# alfred_pulse.net
KiCad netlist of a schematic drawn in EAGLE
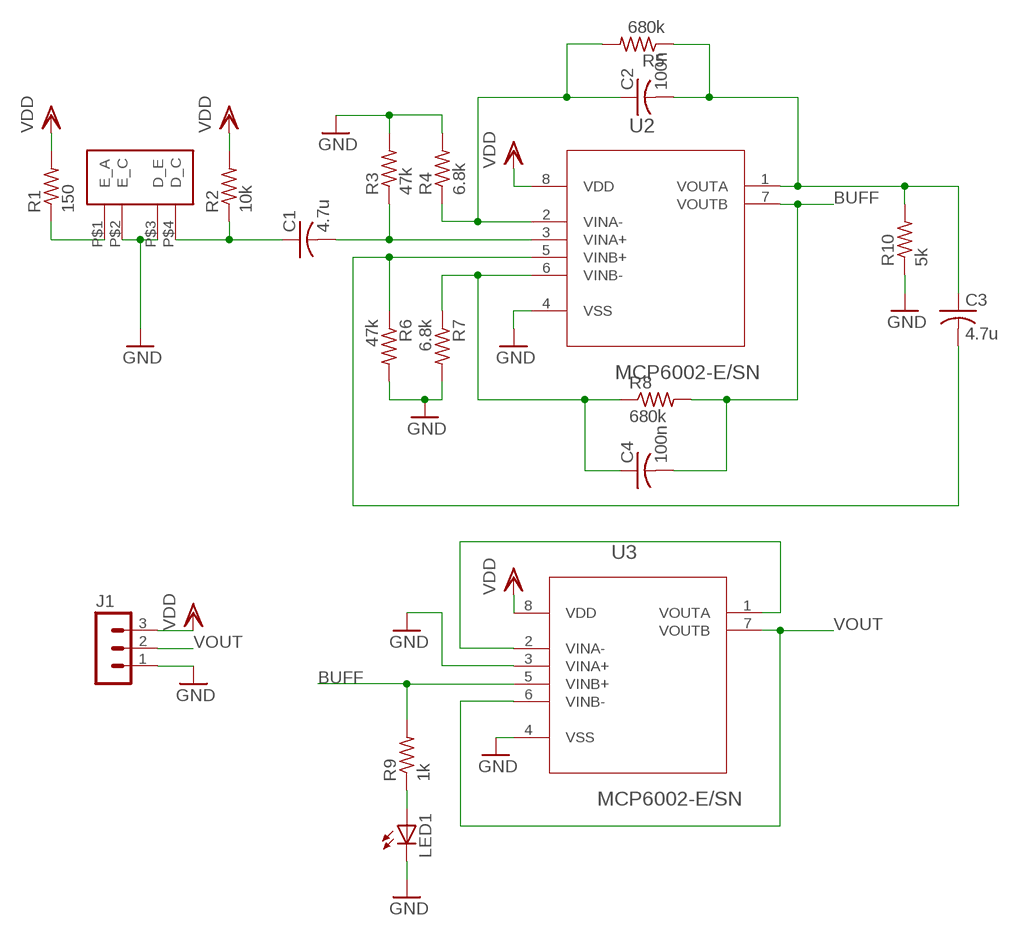
[diagram p0: schematic, sheet 1]

(export (version "E")
  (design (tool "Eeschema 10.0.6"))
  (components
    (comp (ref "C1")
      (value "4.7u")
      (footprint "eagle-import:C0603")
      (libsource (lib "eagle-import") (part "C-USC0603"))
    )
    (comp (ref "C2")
      (value "100n")
      (footprint "eagle-import:C0603")
      (libsource (lib "eagle-import") (part "C-USC0603"))
    )
    (comp (ref "C3")
      (value "4.7u")
      (footprint "eagle-import:C0603")
      (libsource (lib "eagle-import") (part "C-USC0603"))
    )
    (comp (ref "C4")
      (value "100n")
      (footprint "eagle-import:C0603")
      (libsource (lib "eagle-import") (part "C-USC0603"))
    )
    (comp (ref "J1")
      (value "MA03-1")
      (footprint "eagle-import:MA03-1")
      (libsource (lib "eagle-import") (part "MA03-1"))
    )
    (comp (ref "LED1")
      (value "LEDCHIPLED_1206")
      (footprint "eagle-import:CHIPLED_1206")
      (libsource (lib "eagle-import") (part "LEDCHIPLED_1206"))
    )
    (comp (ref "R1")
      (value "150")
      (footprint "eagle-import:R0603")
      (libsource (lib "eagle-import") (part "R-US_R0603"))
    )
    (comp (ref "R2")
      (value "10k")
      (footprint "eagle-import:R0603")
      (libsource (lib "eagle-import") (part "R-US_R0603"))
    )
    (comp (ref "R3")
      (value "47k")
      (footprint "eagle-import:R0603")
      (libsource (lib "eagle-import") (part "R-US_R0603"))
    )
    (comp (ref "R4")
      (value "6.8k")
      (footprint "eagle-import:R0603")
      (libsource (lib "eagle-import") (part "R-US_R0603"))
    )
    (comp (ref "R5")
      (value "680k")
      (footprint "eagle-import:R0603")
      (libsource (lib "eagle-import") (part "R-US_R0603"))
    )
    (comp (ref "R6")
      (value "47k")
      (footprint "eagle-import:R0603")
      (libsource (lib "eagle-import") (part "R-US_R0603"))
    )
    (comp (ref "R7")
      (value "6.8k")
      (footprint "eagle-import:R0603")
      (libsource (lib "eagle-import") (part "R-US_R0603"))
    )
    (comp (ref "R8")
      (value "680k")
      (footprint "eagle-import:R0603")
      (libsource (lib "eagle-import") (part "R-US_R0603"))
    )
    (comp (ref "R9")
      (value "1k")
      (footprint "eagle-import:R0603")
      (libsource (lib "eagle-import") (part "R-US_R0603"))
    )
    (comp (ref "R10")
      (value "5k")
      (footprint "eagle-import:R0603")
      (libsource (lib "eagle-import") (part "R-US_R0603"))
    )
    (comp (ref "U$1")
      (value "TCRT1001")
      (footprint "eagle-import:TCRT1001")
      (libsource (lib "eagle-import") (part "TCRT1001"))
    )
    (comp (ref "U2")
      (value "MCP6002-E/SN")
      (footprint "eagle-import:SOIC127P600X175-8N")
      (libsource (lib "eagle-import") (part "MCP6002-E/SN"))
    )
    (comp (ref "U3")
      (value "MCP6002-E/SN")
      (footprint "eagle-import:SOIC127P600X175-8N")
      (libsource (lib "eagle-import") (part "MCP6002-E/SN"))
    )
  )
  (nets
    (net (code "1") (name "/BUFF") (class "Default")
      (node (ref "C4") (pin "2") (pinfunction "2_2") (pintype "passive"))
      (node (ref "R8") (pin "2") (pinfunction "2_2") (pintype "passive"))
      (node (ref "R9") (pin "2") (pinfunction "2_2") (pintype "passive"))
      (node (ref "U2") (pin "7") (pinfunction "VOUTB_7") (pintype "output"))
      (node (ref "U3") (pin "5") (pinfunction "VINB+_5") (pintype "input"))
    )
    (net (code "2") (name "/VOUT") (class "Default")
      (node (ref "J1") (pin "2") (pinfunction "2_2") (pintype "passive"))
      (node (ref "U3") (pin "6") (pinfunction "VINB-_6") (pintype "input"))
      (node (ref "U3") (pin "7") (pinfunction "VOUTB_7") (pintype "output"))
    )
    (net (code "3") (name "GND") (class "Default")
      (node (ref "J1") (pin "1") (pinfunction "1_1") (pintype "passive"))
      (node (ref "LED1") (pin "C") (pinfunction "C_C") (pintype "passive"))
      (node (ref "R10") (pin "1") (pinfunction "1_1") (pintype "passive"))
      (node (ref "R3") (pin "2") (pinfunction "2_2") (pintype "passive"))
      (node (ref "R4") (pin "2") (pinfunction "2_2") (pintype "passive"))
      (node (ref "R6") (pin "2") (pinfunction "2_2") (pintype "passive"))
      (node (ref "R7") (pin "2") (pinfunction "2_2") (pintype "passive"))
      (node (ref "U$1") (pin "P$2") (pinfunction "E_C_P$2") (pintype "bidirectional"))
      (node (ref "U$1") (pin "P$3") (pinfunction "D_E_P$3") (pintype "bidirectional"))
      (node (ref "U2") (pin "4") (pinfunction "VSS_4") (pintype "power_in"))
      (node (ref "U3") (pin "3") (pinfunction "VINA+_3") (pintype "input"))
      (node (ref "U3") (pin "4") (pinfunction "VSS_4") (pintype "power_in"))
    )
    (net (code "4") (name "Net-(LED1-PadA)") (class "Default")
      (node (ref "LED1") (pin "A") (pinfunction "A_A") (pintype "passive"))
      (node (ref "R9") (pin "1") (pinfunction "1_1") (pintype "passive"))
    )
    (net (code "5") (name "Net-(U$1-D_C)") (class "Default")
      (node (ref "C1") (pin "1") (pinfunction "1_1") (pintype "passive"))
      (node (ref "R2") (pin "1") (pinfunction "1_1") (pintype "passive"))
      (node (ref "U$1") (pin "P$4") (pinfunction "D_C_P$4") (pintype "bidirectional"))
    )
    (net (code "6") (name "Net-(U$1-E_A)") (class "Default")
      (node (ref "R1") (pin "1") (pinfunction "1_1") (pintype "passive"))
      (node (ref "U$1") (pin "P$1") (pinfunction "E_A_P$1") (pintype "bidirectional"))
    )
    (net (code "7") (name "Net-(U2-VINA+)") (class "Default")
      (node (ref "C1") (pin "2") (pinfunction "2_2") (pintype "passive"))
      (node (ref "R3") (pin "1") (pinfunction "1_1") (pintype "passive"))
      (node (ref "U2") (pin "3") (pinfunction "VINA+_3") (pintype "input"))
    )
    (net (code "8") (name "Net-(U2-VINA-)") (class "Default")
      (node (ref "C2") (pin "1") (pinfunction "1_1") (pintype "passive"))
      (node (ref "R4") (pin "1") (pinfunction "1_1") (pintype "passive"))
      (node (ref "R5") (pin "2") (pinfunction "2_2") (pintype "passive"))
      (node (ref "U2") (pin "2") (pinfunction "VINA-_2") (pintype "input"))
    )
    (net (code "9") (name "Net-(U2-VINB+)") (class "Default")
      (node (ref "C3") (pin "2") (pinfunction "2_2") (pintype "passive"))
      (node (ref "R6") (pin "1") (pinfunction "1_1") (pintype "passive"))
      (node (ref "U2") (pin "5") (pinfunction "VINB+_5") (pintype "input"))
    )
    (net (code "10") (name "Net-(U2-VINB-)") (class "Default")
      (node (ref "C4") (pin "1") (pinfunction "1_1") (pintype "passive"))
      (node (ref "R7") (pin "1") (pinfunction "1_1") (pintype "passive"))
      (node (ref "R8") (pin "1") (pinfunction "1_1") (pintype "passive"))
      (node (ref "U2") (pin "6") (pinfunction "VINB-_6") (pintype "input"))
    )
    (net (code "11") (name "Net-(U2-VOUTA)") (class "Default")
      (node (ref "C2") (pin "2") (pinfunction "2_2") (pintype "passive"))
      (node (ref "C3") (pin "1") (pinfunction "1_1") (pintype "passive"))
      (node (ref "R10") (pin "2") (pinfunction "2_2") (pintype "passive"))
      (node (ref "R5") (pin "1") (pinfunction "1_1") (pintype "passive"))
      (node (ref "U2") (pin "1") (pinfunction "VOUTA_1") (pintype "output"))
    )
    (net (code "12") (name "Net-(U3-VINA-)") (class "Default")
      (node (ref "U3") (pin "1") (pinfunction "VOUTA_1") (pintype "output"))
      (node (ref "U3") (pin "2") (pinfunction "VINA-_2") (pintype "input"))
    )
    (net (code "13") (name "VDD") (class "Default")
      (node (ref "J1") (pin "3") (pinfunction "3_3") (pintype "passive"))
      (node (ref "R1") (pin "2") (pinfunction "2_2") (pintype "passive"))
      (node (ref "R2") (pin "2") (pinfunction "2_2") (pintype "passive"))
      (node (ref "U2") (pin "8") (pinfunction "VDD_8") (pintype "power_in"))
      (node (ref "U3") (pin "8") (pinfunction "VDD_8") (pintype "power_in"))
    )
  )
)
